# ACS713-SOIC8.net
KiCad netlist of a schematic drawn in EAGLE
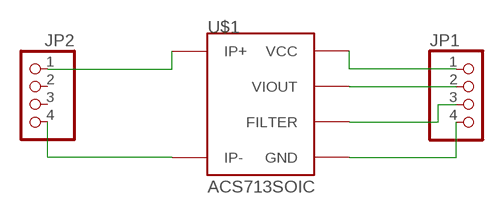
[diagram p0: schematic, sheet 1]

(export (version "E")
  (design (tool "Eeschema 10.0.6"))
  (components
    (comp (ref "JP1")
      (value "PINHD-1X4")
      (footprint "eagle-import:1X04")
      (libsource (lib "eagle-import") (part "PINHD-1X4"))
    )
    (comp (ref "JP2")
      (value "PINHD-1X4")
      (footprint "eagle-import:1X04")
      (libsource (lib "eagle-import") (part "PINHD-1X4"))
    )
    (comp (ref "U$1")
      (value "ACS713SOIC")
      (footprint "eagle-import:ACS713-SOIC")
      (libsource (lib "eagle-import") (part "ACS713SOIC"))
    )
  )
  (nets
    (net (code "1") (name "Net-(JP2-Pad1)") (class "Default")
      (node (ref "JP2") (pin "1") (pinfunction "1_1") (pintype "passive"))
      (node (ref "U$1") (pin "P$1") (pinfunction "IP+_P$1") (pintype "bidirectional"))
      (node (ref "U$1") (pin "P$2") (pinfunction "IP+_P$2") (pintype "bidirectional"))
    )
    (net (code "2") (name "Net-(JP2-Pad4)") (class "Default")
      (node (ref "JP2") (pin "4") (pinfunction "4_4") (pintype "passive"))
      (node (ref "U$1") (pin "P$3") (pinfunction "IP-_P$3") (pintype "bidirectional"))
      (node (ref "U$1") (pin "P$4") (pinfunction "IP-_P$4") (pintype "bidirectional"))
    )
    (net (code "3") (name "Net-(U$1-FILTER)") (class "Default")
      (node (ref "JP1") (pin "3") (pinfunction "3_3") (pintype "passive"))
      (node (ref "U$1") (pin "P$6") (pinfunction "FILTER_P$6") (pintype "bidirectional"))
    )
    (net (code "4") (name "Net-(U$1-GND)") (class "Default")
      (node (ref "JP1") (pin "4") (pinfunction "4_4") (pintype "passive"))
      (node (ref "U$1") (pin "P$5") (pinfunction "GND_P$5") (pintype "bidirectional"))
    )
    (net (code "5") (name "Net-(U$1-VCC)") (class "Default")
      (node (ref "JP1") (pin "1") (pinfunction "1_1") (pintype "passive"))
      (node (ref "U$1") (pin "P$8") (pinfunction "VCC_P$8") (pintype "bidirectional"))
    )
    (net (code "6") (name "Net-(U$1-VIOUT)") (class "Default")
      (node (ref "JP1") (pin "2") (pinfunction "2_2") (pintype "passive"))
      (node (ref "U$1") (pin "P$7") (pinfunction "VIOUT_P$7") (pintype "bidirectional"))
    )
    (net (code "7") (name "unconnected-(JP2-Pad2)") (class "Default")
      (node (ref "JP2") (pin "2") (pinfunction "2_2") (pintype "passive"))
    )
    (net (code "8") (name "unconnected-(JP2-Pad3)") (class "Default")
      (node (ref "JP2") (pin "3") (pinfunction "3_3") (pintype "passive"))
    )
  )
)
